# ProPrj_Low_Taper_Fade_2026-04-30_1.net
KiCad netlist of a schematic drawn in EasyEDA Pro
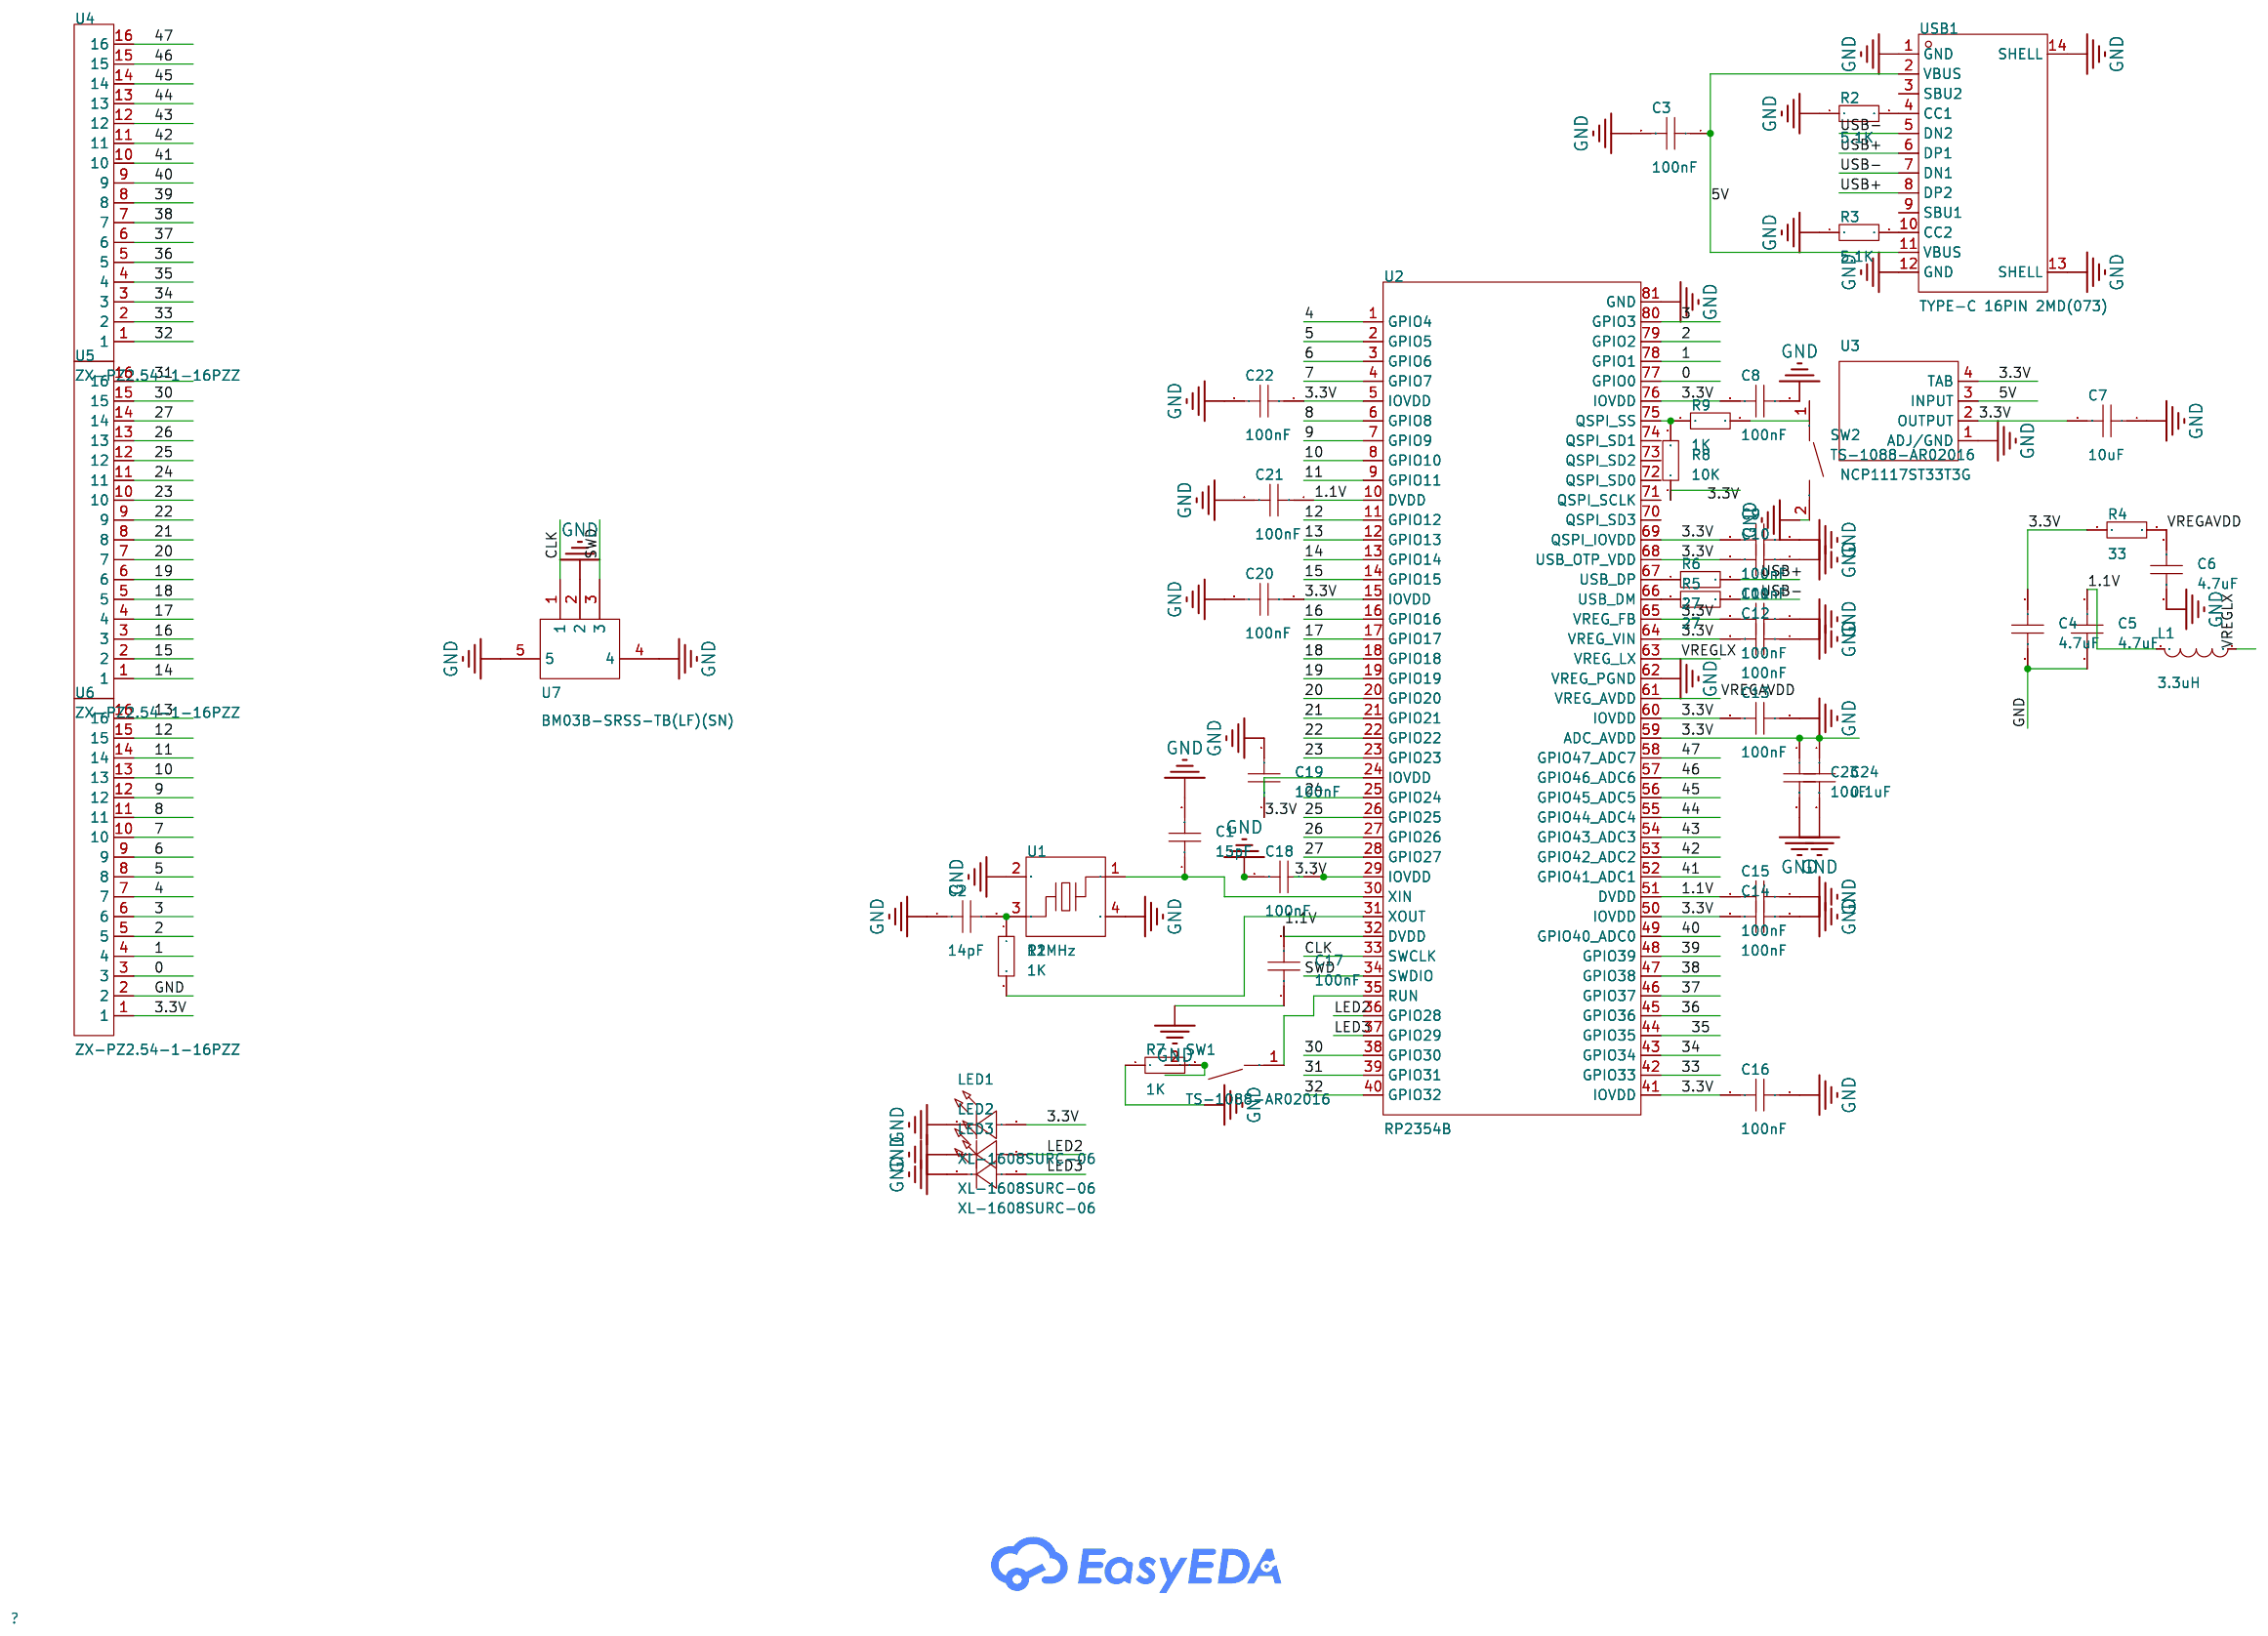
[diagram p0: schematic sheet]

(export (version "E")
  (design (tool "Eeschema 10.0.6"))
  (components
    (comp (ref "C1")
      (value "15pF")
      (footprint "easyedapro:C0603")
      (libsource (lib "easyedapro") (part "CAP"))
    )
    (comp (ref "C2")
      (value "14pF")
      (footprint "easyedapro:C0603")
      (libsource (lib "easyedapro") (part "CAP"))
    )
    (comp (ref "C3")
      (value "100nF")
      (footprint "easyedapro:C0603")
      (libsource (lib "easyedapro") (part "CAP"))
    )
    (comp (ref "C4")
      (value "4.7uF")
      (footprint "easyedapro:C0603")
      (libsource (lib "easyedapro") (part "CAP"))
    )
    (comp (ref "C5")
      (value "4.7uF")
      (footprint "easyedapro:C0603")
      (libsource (lib "easyedapro") (part "CAP"))
    )
    (comp (ref "C6")
      (value "4.7uF")
      (footprint "easyedapro:C0603")
      (libsource (lib "easyedapro") (part "CAP"))
    )
    (comp (ref "C7")
      (value "10uF")
      (footprint "easyedapro:C0603")
      (libsource (lib "easyedapro") (part "CAP"))
    )
    (comp (ref "C8")
      (value "100nF")
      (footprint "easyedapro:C0603")
      (libsource (lib "easyedapro") (part "CAP"))
    )
    (comp (ref "C9")
      (value "100nF")
      (footprint "easyedapro:C0603")
      (libsource (lib "easyedapro") (part "CAP"))
    )
    (comp (ref "C10")
      (value "100nF")
      (footprint "easyedapro:C0603")
      (libsource (lib "easyedapro") (part "CAP"))
    )
    (comp (ref "C11")
      (value "100nF")
      (footprint "easyedapro:C0603")
      (libsource (lib "easyedapro") (part "CAP"))
    )
    (comp (ref "C12")
      (value "100nF")
      (footprint "easyedapro:C0603")
      (libsource (lib "easyedapro") (part "CAP"))
    )
    (comp (ref "C13")
      (value "100nF")
      (footprint "easyedapro:C0603")
      (libsource (lib "easyedapro") (part "CAP"))
    )
    (comp (ref "C14")
      (value "100nF")
      (footprint "easyedapro:C0603")
      (libsource (lib "easyedapro") (part "CAP"))
    )
    (comp (ref "C15")
      (value "100nF")
      (footprint "easyedapro:C0603")
      (libsource (lib "easyedapro") (part "CAP"))
    )
    (comp (ref "C16")
      (value "100nF")
      (footprint "easyedapro:C0603")
      (libsource (lib "easyedapro") (part "CAP"))
    )
    (comp (ref "C17")
      (value "100nF")
      (footprint "easyedapro:C0603")
      (libsource (lib "easyedapro") (part "CAP"))
    )
    (comp (ref "C18")
      (value "100nF")
      (footprint "easyedapro:C0603")
      (libsource (lib "easyedapro") (part "CAP"))
    )
    (comp (ref "C19")
      (value "100nF")
      (footprint "easyedapro:C0603")
      (libsource (lib "easyedapro") (part "CAP"))
    )
    (comp (ref "C20")
      (value "100nF")
      (footprint "easyedapro:C0603")
      (libsource (lib "easyedapro") (part "CAP"))
    )
    (comp (ref "C21")
      (value "100nF")
      (footprint "easyedapro:C0603")
      (libsource (lib "easyedapro") (part "CAP"))
    )
    (comp (ref "C22")
      (value "100nF")
      (footprint "easyedapro:C0603")
      (libsource (lib "easyedapro") (part "CAP"))
    )
    (comp (ref "C23")
      (value "10uF")
      (footprint "easyedapro:C0603")
      (libsource (lib "easyedapro") (part "CAP"))
    )
    (comp (ref "C24")
      (value "0.1uF")
      (footprint "easyedapro:C0603")
      (libsource (lib "easyedapro") (part "CAP"))
    )
    (comp (ref "L1")
      (value "3.3uH")
      (footprint "easyedapro:IND-SMD_L2.0-W1.6_AOTA-B201610S3R3-101-T")
      (fields
        (field (name "Manufacturer Part") "AOTA-B201610S3R3-101-T")
        (field (name "Manufacturer") "ABRACON")
      )
      (libsource (lib "easyedapro") (part "AOTA-B201610S3R3-101-T"))
    )
    (comp (ref "LED1")
      (value "XL-1608SURC-06")
      (footprint "easyedapro:LED0603-RD_RED")
      (fields (field (name "Manufacturer") "XINGLIGHT(成兴光)"))
      (libsource (lib "easyedapro") (part "XL-1608SURC-06"))
    )
    (comp (ref "LED2")
      (value "XL-1608SURC-06")
      (footprint "easyedapro:LED0603-RD_RED")
      (fields (field (name "Manufacturer") "XINGLIGHT(成兴光)"))
      (libsource (lib "easyedapro") (part "XL-1608SURC-06"))
    )
    (comp (ref "LED3")
      (value "XL-1608SURC-06")
      (footprint "easyedapro:LED0603-RD_RED")
      (fields (field (name "Manufacturer") "XINGLIGHT(成兴光)"))
      (libsource (lib "easyedapro") (part "XL-1608SURC-06"))
    )
    (comp (ref "R1") (value "1K") (footprint "easyedapro:R0603") (libsource (lib "easyedapro") (part "Res")))
    (comp (ref "R2")
      (value "5.1K")
      (footprint "easyedapro:R0603")
      (libsource (lib "easyedapro") (part "Res"))
    )
    (comp (ref "R3")
      (value "5.1K")
      (footprint "easyedapro:R0603")
      (libsource (lib "easyedapro") (part "Res"))
    )
    (comp (ref "R4") (value "33") (footprint "easyedapro:R0603") (libsource (lib "easyedapro") (part "Res")))
    (comp (ref "R5") (value "27") (footprint "easyedapro:R0603") (libsource (lib "easyedapro") (part "Res")))
    (comp (ref "R6") (value "27") (footprint "easyedapro:R0603") (libsource (lib "easyedapro") (part "Res")))
    (comp (ref "R7") (value "1K") (footprint "easyedapro:R0603") (libsource (lib "easyedapro") (part "Res")))
    (comp (ref "R8") (value "10K") (footprint "easyedapro:R0603") (libsource (lib "easyedapro") (part "Res")))
    (comp (ref "R9") (value "1K") (footprint "easyedapro:R0603") (libsource (lib "easyedapro") (part "Res")))
    (comp (ref "SW1")
      (value "TS-1088-AR02016")
      (footprint "easyedapro:SW-SMD_L3.9-W3.0-P4.45")
      (fields (field (name "Manufacturer") "XUNPU(讯普)"))
      (libsource (lib "easyedapro") (part "TS-1088-AR02016"))
    )
    (comp (ref "SW2")
      (value "TS-1088-AR02016")
      (footprint "easyedapro:SW-SMD_L3.9-W3.0-P4.45")
      (fields (field (name "Manufacturer") "XUNPU(讯普)"))
      (libsource (lib "easyedapro") (part "TS-1088-AR02016"))
    )
    (comp (ref "U1")
      (value "12MHz")
      (footprint "easyedapro:CRYSTAL-SMD_4P-L3.2-W2.5-BL")
      (fields (field (name "Manufacturer Part") "ABM8-272-T3") (field (name "Manufacturer") "ABRACON"))
      (libsource (lib "easyedapro") (part "ABM8-272-T3_C20625731"))
    )
    (comp (ref "U2")
      (value "RP2354B")
      (footprint "easyedapro:QFN-80_L10.0-W10.0-P0.40-TL-EP3.4")
      (description "Features:True random number generator (TRNG)；External pin reset (NRST)")
      (fields (field (name "Manufacturer") "Raspberry Pi(树莓派)"))
      (libsource (lib "easyedapro") (part "RP2354B_C39843328"))
    )
    (comp (ref "U3")
      (value "NCP1117ST33T3G")
      (footprint "easyedapro:SOT-223-3_L6.5-W3.4-P2.30-LS7.0-BR")
      (fields (field (name "Manufacturer") "onsemi(安森美)"))
      (libsource (lib "easyedapro") (part "NCP1117ST33T3G"))
    )
    (comp (ref "U4")
      (value "ZX-PZ2.54-1-16PZZ")
      (footprint "easyedapro:HDR-TH_16P-P2.54-V-M-2")
      (fields (field (name "Manufacturer") "Megastar(兆星)"))
      (libsource (lib "easyedapro") (part "ZX-PZ2.54-1-16PZZ"))
    )
    (comp (ref "U5")
      (value "ZX-PZ2.54-1-16PZZ")
      (footprint "easyedapro:HDR-TH_16P-P2.54-V-M-2")
      (fields (field (name "Manufacturer") "Megastar(兆星)"))
      (libsource (lib "easyedapro") (part "ZX-PZ2.54-1-16PZZ"))
    )
    (comp (ref "U6")
      (value "ZX-PZ2.54-1-16PZZ")
      (footprint "easyedapro:HDR-TH_16P-P2.54-V-M-2")
      (fields (field (name "Manufacturer") "Megastar(兆星)"))
      (libsource (lib "easyedapro") (part "ZX-PZ2.54-1-16PZZ"))
    )
    (comp (ref "U7")
      (value "BM03B-SRSS-TB(LF)(SN)")
      (footprint "easyedapro:CONN-SMD-3P-P1.00_BM03B-SRSS-TB-LF-SN")
      (fields (field (name "Manufacturer") "JST"))
      (libsource (lib "easyedapro") (part "BM03B-SRSS-TB(LF)(SN)"))
    )
    (comp (ref "USB1")
      (value "TYPE-C 16PIN 2MD(073)")
      (footprint "easyedapro:USB-C-SMD_TYPE-C-6PIN-2MD-073")
      (fields (field (name "Manufacturer") "SHOU HAN(首韩)"))
      (libsource (lib "easyedapro") (part "TYPE-C 16PIN 2MD(073)"))
    )
  )
  (nets
    (net (code "1") (name "/0") (class "Default")
      (node (ref "U2") (pin "77") (pinfunction "GPIO0_77") (pintype "unspecified"))
      (node (ref "U6") (pin "3") (pinfunction "3_3") (pintype "unspecified"))
    )
    (net (code "2") (name "/1") (class "Default")
      (node (ref "U2") (pin "78") (pinfunction "GPIO1_78") (pintype "unspecified"))
      (node (ref "U6") (pin "4") (pinfunction "4_4") (pintype "unspecified"))
    )
    (net (code "3") (name "/1.1V") (class "Default")
      (node (ref "C15") (pin "2") (pinfunction "2_2") (pintype "input"))
      (node (ref "C17") (pin "2") (pinfunction "2_2") (pintype "input"))
      (node (ref "C21") (pin "1") (pinfunction "1_1") (pintype "input"))
      (node (ref "C5") (pin "1") (pinfunction "1_1") (pintype "input"))
      (node (ref "L1") (pin "2") (pinfunction "2_2") (pintype "unspecified"))
      (node (ref "U2") (pin "10") (pinfunction "DVDD_10") (pintype "unspecified"))
      (node (ref "U2") (pin "32") (pinfunction "DVDD_32") (pintype "unspecified"))
      (node (ref "U2") (pin "51") (pinfunction "DVDD_51") (pintype "unspecified"))
    )
    (net (code "4") (name "/2") (class "Default")
      (node (ref "U2") (pin "79") (pinfunction "GPIO2_79") (pintype "unspecified"))
      (node (ref "U6") (pin "5") (pinfunction "5_5") (pintype "unspecified"))
    )
    (net (code "5") (name "/3") (class "Default")
      (node (ref "U2") (pin "80") (pinfunction "GPIO3_80") (pintype "unspecified"))
      (node (ref "U6") (pin "6") (pinfunction "6_6") (pintype "unspecified"))
    )
    (net (code "6") (name "/3.3V") (class "Default")
      (node (ref "C10") (pin "2") (pinfunction "2_2") (pintype "input"))
      (node (ref "C11") (pin "2") (pinfunction "2_2") (pintype "input"))
      (node (ref "C12") (pin "2") (pinfunction "2_2") (pintype "input"))
      (node (ref "C13") (pin "2") (pinfunction "2_2") (pintype "input"))
      (node (ref "C14") (pin "2") (pinfunction "2_2") (pintype "input"))
      (node (ref "C16") (pin "2") (pinfunction "2_2") (pintype "input"))
      (node (ref "C18") (pin "1") (pinfunction "1_1") (pintype "input"))
      (node (ref "C19") (pin "1") (pinfunction "1_1") (pintype "input"))
      (node (ref "C20") (pin "1") (pinfunction "1_1") (pintype "input"))
      (node (ref "C22") (pin "1") (pinfunction "1_1") (pintype "input"))
      (node (ref "C23") (pin "1") (pinfunction "1_1") (pintype "input"))
      (node (ref "C24") (pin "1") (pinfunction "1_1") (pintype "input"))
      (node (ref "C4") (pin "1") (pinfunction "1_1") (pintype "input"))
      (node (ref "C7") (pin "2") (pinfunction "2_2") (pintype "input"))
      (node (ref "C8") (pin "2") (pinfunction "2_2") (pintype "input"))
      (node (ref "C9") (pin "2") (pinfunction "2_2") (pintype "input"))
      (node (ref "LED1") (pin "2") (pinfunction "A_2") (pintype "unspecified"))
      (node (ref "R4") (pin "1") (pinfunction "1_1") (pintype "input"))
      (node (ref "R8") (pin "1") (pinfunction "1_1") (pintype "input"))
      (node (ref "U2") (pin "15") (pinfunction "IOVDD_15") (pintype "unspecified"))
      (node (ref "U2") (pin "24") (pinfunction "IOVDD_24") (pintype "unspecified"))
      (node (ref "U2") (pin "29") (pinfunction "IOVDD_29") (pintype "unspecified"))
      (node (ref "U2") (pin "41") (pinfunction "IOVDD_41") (pintype "unspecified"))
      (node (ref "U2") (pin "5") (pinfunction "IOVDD_5") (pintype "unspecified"))
      (node (ref "U2") (pin "50") (pinfunction "IOVDD_50") (pintype "unspecified"))
      (node (ref "U2") (pin "59") (pinfunction "ADC_AVDD_59") (pintype "unspecified"))
      (node (ref "U2") (pin "60") (pinfunction "IOVDD_60") (pintype "unspecified"))
      (node (ref "U2") (pin "64") (pinfunction "VREG_VIN_64") (pintype "unspecified"))
      (node (ref "U2") (pin "65") (pinfunction "VREG_FB_65") (pintype "unspecified"))
      (node (ref "U2") (pin "68") (pinfunction "USB_OTP_VDD_68") (pintype "unspecified"))
      (node (ref "U2") (pin "69") (pinfunction "QSPI_IOVDD_69") (pintype "unspecified"))
      (node (ref "U2") (pin "76") (pinfunction "IOVDD_76") (pintype "unspecified"))
      (node (ref "U3") (pin "2") (pinfunction "OUTPUT_2") (pintype "unspecified"))
      (node (ref "U3") (pin "4") (pinfunction "TAB_4") (pintype "unspecified"))
      (node (ref "U6") (pin "1") (pinfunction "1_1") (pintype "unspecified"))
    )
    (net (code "7") (name "/4") (class "Default")
      (node (ref "U2") (pin "1") (pinfunction "GPIO4_1") (pintype "unspecified"))
      (node (ref "U6") (pin "7") (pinfunction "7_7") (pintype "unspecified"))
    )
    (net (code "8") (name "/5") (class "Default")
      (node (ref "U2") (pin "2") (pinfunction "GPIO5_2") (pintype "unspecified"))
      (node (ref "U6") (pin "8") (pinfunction "8_8") (pintype "unspecified"))
    )
    (net (code "9") (name "/5V") (class "Default")
      (node (ref "C3") (pin "1") (pinfunction "1_1") (pintype "input"))
      (node (ref "U3") (pin "3") (pinfunction "INPUT_3") (pintype "unspecified"))
      (node (ref "USB1") (pin "11") (pinfunction "VBUS_11") (pintype "unspecified"))
      (node (ref "USB1") (pin "2") (pinfunction "VBUS_2") (pintype "unspecified"))
    )
    (net (code "10") (name "/6") (class "Default")
      (node (ref "U2") (pin "3") (pinfunction "GPIO6_3") (pintype "unspecified"))
      (node (ref "U6") (pin "9") (pinfunction "9_9") (pintype "unspecified"))
    )
    (net (code "11") (name "/7") (class "Default")
      (node (ref "U2") (pin "4") (pinfunction "GPIO7_4") (pintype "unspecified"))
      (node (ref "U6") (pin "10") (pinfunction "10_10") (pintype "unspecified"))
    )
    (net (code "12") (name "/8") (class "Default")
      (node (ref "U2") (pin "6") (pinfunction "GPIO8_6") (pintype "unspecified"))
      (node (ref "U6") (pin "11") (pinfunction "11_11") (pintype "unspecified"))
    )
    (net (code "13") (name "/9") (class "Default")
      (node (ref "U2") (pin "7") (pinfunction "GPIO9_7") (pintype "unspecified"))
      (node (ref "U6") (pin "12") (pinfunction "12_12") (pintype "unspecified"))
    )
    (net (code "14") (name "/10") (class "Default")
      (node (ref "U2") (pin "8") (pinfunction "GPIO10_8") (pintype "unspecified"))
      (node (ref "U6") (pin "13") (pinfunction "13_13") (pintype "unspecified"))
    )
    (net (code "15") (name "/11") (class "Default")
      (node (ref "U2") (pin "9") (pinfunction "GPIO11_9") (pintype "unspecified"))
      (node (ref "U6") (pin "14") (pinfunction "14_14") (pintype "unspecified"))
    )
    (net (code "16") (name "/12") (class "Default")
      (node (ref "U2") (pin "11") (pinfunction "GPIO12_11") (pintype "unspecified"))
      (node (ref "U6") (pin "15") (pinfunction "15_15") (pintype "unspecified"))
    )
    (net (code "17") (name "/13") (class "Default")
      (node (ref "U2") (pin "12") (pinfunction "GPIO13_12") (pintype "unspecified"))
      (node (ref "U6") (pin "16") (pinfunction "16_16") (pintype "unspecified"))
    )
    (net (code "18") (name "/14") (class "Default")
      (node (ref "U2") (pin "13") (pinfunction "GPIO14_13") (pintype "unspecified"))
      (node (ref "U5") (pin "1") (pinfunction "1_1") (pintype "unspecified"))
    )
    (net (code "19") (name "/15") (class "Default")
      (node (ref "U2") (pin "14") (pinfunction "GPIO15_14") (pintype "unspecified"))
      (node (ref "U5") (pin "2") (pinfunction "2_2") (pintype "unspecified"))
    )
    (net (code "20") (name "/16") (class "Default")
      (node (ref "U2") (pin "16") (pinfunction "GPIO16_16") (pintype "unspecified"))
      (node (ref "U5") (pin "3") (pinfunction "3_3") (pintype "unspecified"))
    )
    (net (code "21") (name "/17") (class "Default")
      (node (ref "U2") (pin "17") (pinfunction "GPIO17_17") (pintype "unspecified"))
      (node (ref "U5") (pin "4") (pinfunction "4_4") (pintype "unspecified"))
    )
    (net (code "22") (name "/18") (class "Default")
      (node (ref "U2") (pin "18") (pinfunction "GPIO18_18") (pintype "unspecified"))
      (node (ref "U5") (pin "5") (pinfunction "5_5") (pintype "unspecified"))
    )
    (net (code "23") (name "/19") (class "Default")
      (node (ref "U2") (pin "19") (pinfunction "GPIO19_19") (pintype "unspecified"))
      (node (ref "U5") (pin "6") (pinfunction "6_6") (pintype "unspecified"))
    )
    (net (code "24") (name "/20") (class "Default")
      (node (ref "U2") (pin "20") (pinfunction "GPIO20_20") (pintype "unspecified"))
      (node (ref "U5") (pin "7") (pinfunction "7_7") (pintype "unspecified"))
    )
    (net (code "25") (name "/21") (class "Default")
      (node (ref "U2") (pin "21") (pinfunction "GPIO21_21") (pintype "unspecified"))
      (node (ref "U5") (pin "8") (pinfunction "8_8") (pintype "unspecified"))
    )
    (net (code "26") (name "/22") (class "Default")
      (node (ref "U2") (pin "22") (pinfunction "GPIO22_22") (pintype "unspecified"))
      (node (ref "U5") (pin "9") (pinfunction "9_9") (pintype "unspecified"))
    )
    (net (code "27") (name "/23") (class "Default")
      (node (ref "U2") (pin "23") (pinfunction "GPIO23_23") (pintype "unspecified"))
      (node (ref "U5") (pin "10") (pinfunction "10_10") (pintype "unspecified"))
    )
    (net (code "28") (name "/24") (class "Default")
      (node (ref "U2") (pin "25") (pinfunction "GPIO24_25") (pintype "unspecified"))
      (node (ref "U5") (pin "11") (pinfunction "11_11") (pintype "unspecified"))
    )
    (net (code "29") (name "/25") (class "Default")
      (node (ref "U2") (pin "26") (pinfunction "GPIO25_26") (pintype "unspecified"))
      (node (ref "U5") (pin "12") (pinfunction "12_12") (pintype "unspecified"))
    )
    (net (code "30") (name "/26") (class "Default")
      (node (ref "U2") (pin "27") (pinfunction "GPIO26_27") (pintype "unspecified"))
      (node (ref "U5") (pin "13") (pinfunction "13_13") (pintype "unspecified"))
    )
    (net (code "31") (name "/27") (class "Default")
      (node (ref "U2") (pin "28") (pinfunction "GPIO27_28") (pintype "unspecified"))
      (node (ref "U5") (pin "14") (pinfunction "14_14") (pintype "unspecified"))
    )
    (net (code "32") (name "/30") (class "Default")
      (node (ref "U2") (pin "38") (pinfunction "GPIO30_38") (pintype "unspecified"))
      (node (ref "U5") (pin "15") (pinfunction "15_15") (pintype "unspecified"))
    )
    (net (code "33") (name "/31") (class "Default")
      (node (ref "U2") (pin "39") (pinfunction "GPIO31_39") (pintype "unspecified"))
      (node (ref "U5") (pin "16") (pinfunction "16_16") (pintype "unspecified"))
    )
    (net (code "34") (name "/32") (class "Default")
      (node (ref "U2") (pin "40") (pinfunction "GPIO32_40") (pintype "unspecified"))
      (node (ref "U4") (pin "1") (pinfunction "1_1") (pintype "unspecified"))
    )
    (net (code "35") (name "/33") (class "Default")
      (node (ref "U2") (pin "42") (pinfunction "GPIO33_42") (pintype "unspecified"))
      (node (ref "U4") (pin "2") (pinfunction "2_2") (pintype "unspecified"))
    )
    (net (code "36") (name "/34") (class "Default")
      (node (ref "U2") (pin "43") (pinfunction "GPIO34_43") (pintype "unspecified"))
      (node (ref "U4") (pin "3") (pinfunction "3_3") (pintype "unspecified"))
    )
    (net (code "37") (name "/35") (class "Default")
      (node (ref "U2") (pin "44") (pinfunction "GPIO35_44") (pintype "unspecified"))
      (node (ref "U4") (pin "4") (pinfunction "4_4") (pintype "unspecified"))
    )
    (net (code "38") (name "/36") (class "Default")
      (node (ref "U2") (pin "45") (pinfunction "GPIO36_45") (pintype "unspecified"))
      (node (ref "U4") (pin "5") (pinfunction "5_5") (pintype "unspecified"))
    )
    (net (code "39") (name "/37") (class "Default")
      (node (ref "U2") (pin "46") (pinfunction "GPIO37_46") (pintype "unspecified"))
      (node (ref "U4") (pin "6") (pinfunction "6_6") (pintype "unspecified"))
    )
    (net (code "40") (name "/38") (class "Default")
      (node (ref "U2") (pin "47") (pinfunction "GPIO38_47") (pintype "unspecified"))
      (node (ref "U4") (pin "7") (pinfunction "7_7") (pintype "unspecified"))
    )
    (net (code "41") (name "/39") (class "Default")
      (node (ref "U2") (pin "48") (pinfunction "GPIO39_48") (pintype "unspecified"))
      (node (ref "U4") (pin "8") (pinfunction "8_8") (pintype "unspecified"))
    )
    (net (code "42") (name "/40") (class "Default")
      (node (ref "U2") (pin "49") (pinfunction "GPIO40_ADC0_49") (pintype "unspecified"))
      (node (ref "U4") (pin "9") (pinfunction "9_9") (pintype "unspecified"))
    )
    (net (code "43") (name "/41") (class "Default")
      (node (ref "U2") (pin "52") (pinfunction "GPIO41_ADC1_52") (pintype "unspecified"))
      (node (ref "U4") (pin "10") (pinfunction "10_10") (pintype "unspecified"))
    )
    (net (code "44") (name "/42") (class "Default")
      (node (ref "U2") (pin "53") (pinfunction "GPIO42_ADC2_53") (pintype "unspecified"))
      (node (ref "U4") (pin "11") (pinfunction "11_11") (pintype "unspecified"))
    )
    (net (code "45") (name "/43") (class "Default")
      (node (ref "U2") (pin "54") (pinfunction "GPIO43_ADC3_54") (pintype "unspecified"))
      (node (ref "U4") (pin "12") (pinfunction "12_12") (pintype "unspecified"))
    )
    (net (code "46") (name "/44") (class "Default")
      (node (ref "U2") (pin "55") (pinfunction "GPIO44_ADC4_55") (pintype "unspecified"))
      (node (ref "U4") (pin "13") (pinfunction "13_13") (pintype "unspecified"))
    )
    (net (code "47") (name "/45") (class "Default")
      (node (ref "U2") (pin "56") (pinfunction "GPIO45_ADC5_56") (pintype "unspecified"))
      (node (ref "U4") (pin "14") (pinfunction "14_14") (pintype "unspecified"))
    )
    (net (code "48") (name "/46") (class "Default")
      (node (ref "U2") (pin "57") (pinfunction "GPIO46_ADC6_57") (pintype "unspecified"))
      (node (ref "U4") (pin "15") (pinfunction "15_15") (pintype "unspecified"))
    )
    (net (code "49") (name "/47") (class "Default")
      (node (ref "U2") (pin "58") (pinfunction "GPIO47_ADC7_58") (pintype "unspecified"))
      (node (ref "U4") (pin "16") (pinfunction "16_16") (pintype "unspecified"))
    )
    (net (code "50") (name "/CLK") (class "Default")
      (node (ref "U2") (pin "33") (pinfunction "SWCLK_33") (pintype "unspecified"))
      (node (ref "U7") (pin "1") (pinfunction "1_1") (pintype "unspecified"))
    )
    (net (code "51") (name "/LED2") (class "Default")
      (node (ref "LED2") (pin "2") (pinfunction "A_2") (pintype "unspecified"))
      (node (ref "U2") (pin "36") (pinfunction "GPIO28_36") (pintype "unspecified"))
    )
    (net (code "52") (name "/LED3") (class "Default")
      (node (ref "LED3") (pin "2") (pinfunction "A_2") (pintype "unspecified"))
      (node (ref "U2") (pin "37") (pinfunction "GPIO29_37") (pintype "unspecified"))
    )
    (net (code "53") (name "/SWD") (class "Default")
      (node (ref "U2") (pin "34") (pinfunction "SWDIO_34") (pintype "unspecified"))
      (node (ref "U7") (pin "3") (pinfunction "3_3") (pintype "unspecified"))
    )
    (net (code "54") (name "/USB+") (class "Default")
      (node (ref "R6") (pin "2") (pinfunction "2_2") (pintype "input"))
      (node (ref "USB1") (pin "6") (pinfunction "DP1_6") (pintype "unspecified"))
      (node (ref "USB1") (pin "8") (pinfunction "DP2_8") (pintype "unspecified"))
    )
    (net (code "55") (name "/USB-") (class "Default")
      (node (ref "R5") (pin "2") (pinfunction "2_2") (pintype "input"))
      (node (ref "USB1") (pin "5") (pinfunction "DN2_5") (pintype "unspecified"))
      (node (ref "USB1") (pin "7") (pinfunction "DN1_7") (pintype "unspecified"))
    )
    (net (code "56") (name "/VREGAVDD") (class "Default")
      (node (ref "C6") (pin "1") (pinfunction "1_1") (pintype "input"))
      (node (ref "R4") (pin "2") (pinfunction "2_2") (pintype "input"))
      (node (ref "U2") (pin "61") (pinfunction "VREG_AVDD_61") (pintype "unspecified"))
    )
    (net (code "57") (name "/VREGLX") (class "Default")
      (node (ref "L1") (pin "1") (pinfunction "1_1") (pintype "unspecified"))
      (node (ref "U2") (pin "63") (pinfunction "VREG_LX_63") (pintype "unspecified"))
    )
    (net (code "58") (name "GND") (class "Default")
      (node (ref "C1") (pin "2") (pinfunction "2_2") (pintype "input"))
      (node (ref "C10") (pin "1") (pinfunction "1_1") (pintype "input"))
      (node (ref "C11") (pin "1") (pinfunction "1_1") (pintype "input"))
      (node (ref "C12") (pin "1") (pinfunction "1_1") (pintype "input"))
      (node (ref "C13") (pin "1") (pinfunction "1_1") (pintype "input"))
      (node (ref "C14") (pin "1") (pinfunction "1_1") (pintype "input"))
      (node (ref "C15") (pin "1") (pinfunction "1_1") (pintype "input"))
      (node (ref "C16") (pin "1") (pinfunction "1_1") (pintype "input"))
      (node (ref "C17") (pin "1") (pinfunction "1_1") (pintype "input"))
      (node (ref "C18") (pin "2") (pinfunction "2_2") (pintype "input"))
      (node (ref "C19") (pin "2") (pinfunction "2_2") (pintype "input"))
      (node (ref "C2") (pin "1") (pinfunction "1_1") (pintype "input"))
      (node (ref "C20") (pin "2") (pinfunction "2_2") (pintype "input"))
      (node (ref "C21") (pin "2") (pinfunction "2_2") (pintype "input"))
      (node (ref "C22") (pin "2") (pinfunction "2_2") (pintype "input"))
      (node (ref "C23") (pin "2") (pinfunction "2_2") (pintype "input"))
      (node (ref "C24") (pin "2") (pinfunction "2_2") (pintype "input"))
      (node (ref "C3") (pin "2") (pinfunction "2_2") (pintype "input"))
      (node (ref "C4") (pin "2") (pinfunction "2_2") (pintype "input"))
      (node (ref "C5") (pin "2") (pinfunction "2_2") (pintype "input"))
      (node (ref "C6") (pin "2") (pinfunction "2_2") (pintype "input"))
      (node (ref "C7") (pin "1") (pinfunction "1_1") (pintype "input"))
      (node (ref "C8") (pin "1") (pinfunction "1_1") (pintype "input"))
      (node (ref "C9") (pin "1") (pinfunction "1_1") (pintype "input"))
      (node (ref "LED1") (pin "1") (pinfunction "K_1") (pintype "unspecified"))
      (node (ref "LED2") (pin "1") (pinfunction "K_1") (pintype "unspecified"))
      (node (ref "LED3") (pin "1") (pinfunction "K_1") (pintype "unspecified"))
      (node (ref "R2") (pin "1") (pinfunction "1_1") (pintype "input"))
      (node (ref "R3") (pin "1") (pinfunction "1_1") (pintype "input"))
      (node (ref "R7") (pin "1") (pinfunction "1_1") (pintype "input"))
      (node (ref "SW2") (pin "2") (pinfunction "2_2") (pintype "unspecified"))
      (node (ref "U1") (pin "2") (pinfunction "GND_2") (pintype "input"))
      (node (ref "U1") (pin "4") (pinfunction "GND_4") (pintype "input"))
      (node (ref "U2") (pin "62") (pinfunction "VREG_PGND_62") (pintype "unspecified"))
      (node (ref "U2") (pin "81") (pinfunction "GND_81") (pintype "unspecified"))
      (node (ref "U3") (pin "1") (pinfunction "ADJ/GND_1") (pintype "unspecified"))
      (node (ref "U6") (pin "2") (pinfunction "2_2") (pintype "unspecified"))
      (node (ref "U7") (pin "2") (pinfunction "2_2") (pintype "unspecified"))
      (node (ref "U7") (pin "4") (pinfunction "4_4") (pintype "unspecified"))
      (node (ref "U7") (pin "5") (pinfunction "5_5") (pintype "unspecified"))
      (node (ref "USB1") (pin "1") (pinfunction "GND_1") (pintype "unspecified"))
      (node (ref "USB1") (pin "12") (pinfunction "GND_12") (pintype "unspecified"))
      (node (ref "USB1") (pin "13") (pinfunction "SHELL_13") (pintype "unspecified"))
      (node (ref "USB1") (pin "14") (pinfunction "SHELL_14") (pintype "unspecified"))
    )
    (net (code "59") (name "Net-(C2-Pad2)") (class "Default")
      (node (ref "C2") (pin "2") (pinfunction "2_2") (pintype "input"))
      (node (ref "R1") (pin "1") (pinfunction "1_1") (pintype "input"))
      (node (ref "U1") (pin "3") (pinfunction "3_3") (pintype "input"))
    )
    (net (code "60") (name "Net-(R7-Pad2)") (class "Default")
      (node (ref "R7") (pin "2") (pinfunction "2_2") (pintype "input"))
      (node (ref "SW1") (pin "2") (pinfunction "2_2") (pintype "unspecified"))
    )
    (net (code "61") (name "Net-(R9-Pad1)") (class "Default")
      (node (ref "R9") (pin "1") (pinfunction "1_1") (pintype "input"))
      (node (ref "SW2") (pin "1") (pinfunction "1_1") (pintype "unspecified"))
    )
    (net (code "62") (name "Net-(U2-QSPI_SS)") (class "Default")
      (node (ref "R8") (pin "2") (pinfunction "2_2") (pintype "input"))
      (node (ref "R9") (pin "2") (pinfunction "2_2") (pintype "input"))
      (node (ref "U2") (pin "75") (pinfunction "QSPI_SS_75") (pintype "unspecified"))
    )
    (net (code "63") (name "Net-(U2-RUN)") (class "Default")
      (node (ref "SW1") (pin "1") (pinfunction "1_1") (pintype "unspecified"))
      (node (ref "U2") (pin "35") (pinfunction "RUN_35") (pintype "unspecified"))
    )
    (net (code "64") (name "Net-(U2-USB_DM)") (class "Default")
      (node (ref "R5") (pin "1") (pinfunction "1_1") (pintype "input"))
      (node (ref "U2") (pin "66") (pinfunction "USB_DM_66") (pintype "unspecified"))
    )
    (net (code "65") (name "Net-(U2-USB_DP)") (class "Default")
      (node (ref "R6") (pin "1") (pinfunction "1_1") (pintype "input"))
      (node (ref "U2") (pin "67") (pinfunction "USB_DP_67") (pintype "unspecified"))
    )
    (net (code "66") (name "Net-(U2-XIN)") (class "Default")
      (node (ref "C1") (pin "1") (pinfunction "1_1") (pintype "input"))
      (node (ref "U1") (pin "1") (pinfunction "1_1") (pintype "input"))
      (node (ref "U2") (pin "30") (pinfunction "XIN_30") (pintype "unspecified"))
    )
    (net (code "67") (name "Net-(U2-XOUT)") (class "Default")
      (node (ref "R1") (pin "2") (pinfunction "2_2") (pintype "input"))
      (node (ref "U2") (pin "31") (pinfunction "XOUT_31") (pintype "unspecified"))
    )
    (net (code "68") (name "Net-(USB1-CC1)") (class "Default")
      (node (ref "R2") (pin "2") (pinfunction "2_2") (pintype "input"))
      (node (ref "USB1") (pin "4") (pinfunction "CC1_4") (pintype "unspecified"))
    )
    (net (code "69") (name "Net-(USB1-CC2)") (class "Default")
      (node (ref "R3") (pin "2") (pinfunction "2_2") (pintype "input"))
      (node (ref "USB1") (pin "10") (pinfunction "CC2_10") (pintype "unspecified"))
    )
    (net (code "70") (name "unconnected-(U2-QSPI_SCLK-Pad71)") (class "Default")
      (node (ref "U2") (pin "71") (pinfunction "QSPI_SCLK_71") (pintype "unspecified"))
    )
    (net (code "71") (name "unconnected-(U2-QSPI_SD0-Pad72)") (class "Default")
      (node (ref "U2") (pin "72") (pinfunction "QSPI_SD0_72") (pintype "unspecified"))
    )
    (net (code "72") (name "unconnected-(U2-QSPI_SD1-Pad74)") (class "Default")
      (node (ref "U2") (pin "74") (pinfunction "QSPI_SD1_74") (pintype "unspecified"))
    )
    (net (code "73") (name "unconnected-(U2-QSPI_SD2-Pad73)") (class "Default")
      (node (ref "U2") (pin "73") (pinfunction "QSPI_SD2_73") (pintype "unspecified"))
    )
    (net (code "74") (name "unconnected-(U2-QSPI_SD3-Pad70)") (class "Default")
      (node (ref "U2") (pin "70") (pinfunction "QSPI_SD3_70") (pintype "unspecified"))
    )
    (net (code "75") (name "unconnected-(USB1-SBU1-Pad9)") (class "Default")
      (node (ref "USB1") (pin "9") (pinfunction "SBU1_9") (pintype "unspecified"))
    )
    (net (code "76") (name "unconnected-(USB1-SBU2-Pad3)") (class "Default")
      (node (ref "USB1") (pin "3") (pinfunction "SBU2_3") (pintype "unspecified"))
    )
  )
)
